# OpenBLC_CONNECTIONS.net
KiCad netlist of a schematic drawn in Altium Designer
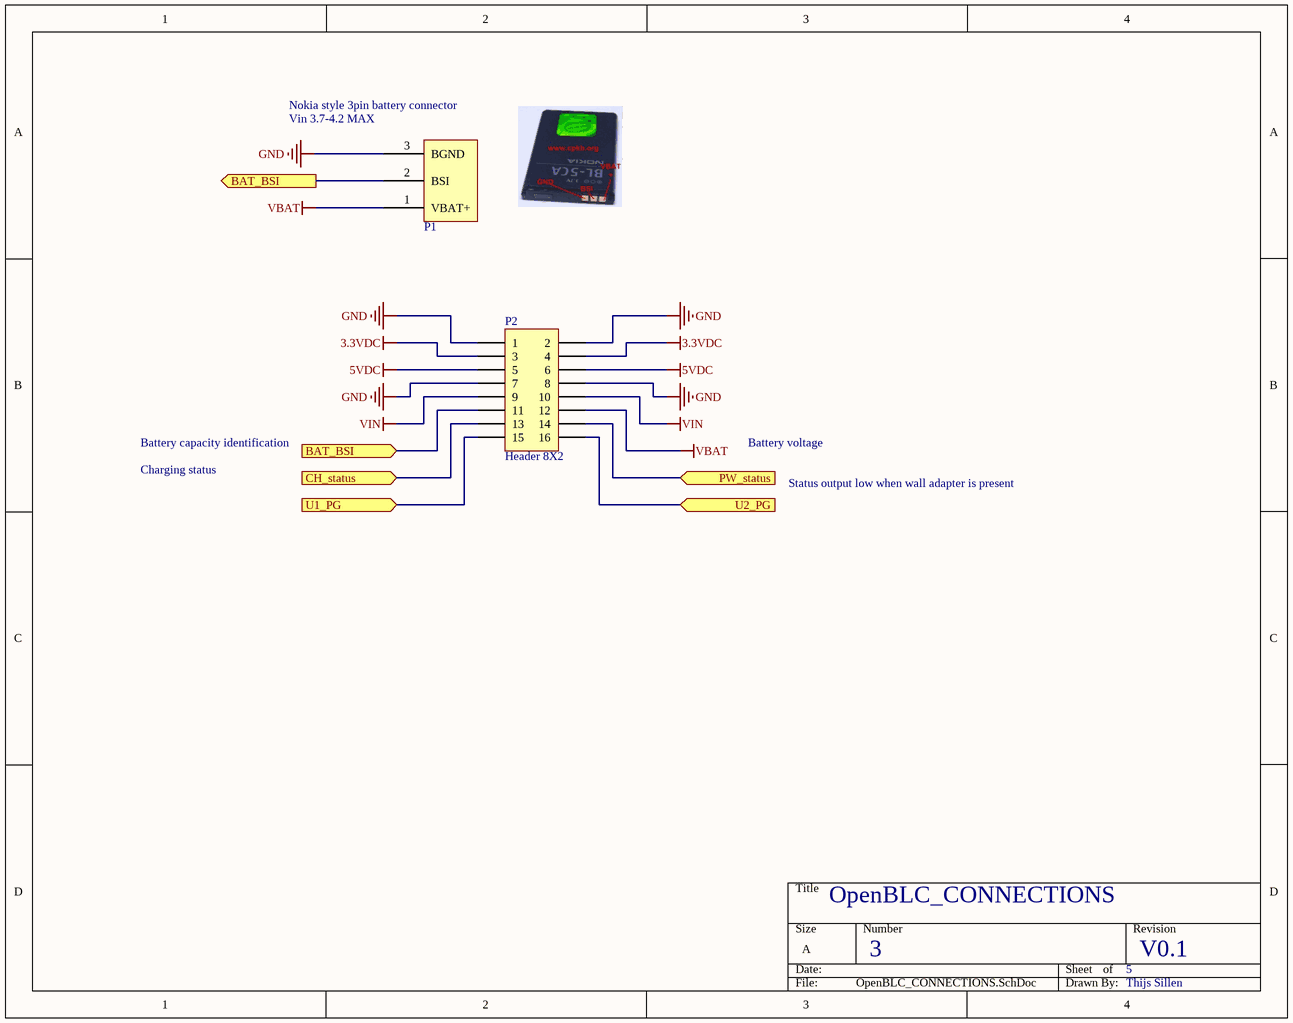
[diagram p0: OpenBLC_CONNECTIONS.SchDoc]

(export (version "E")
  (design (tool "Eeschema 10.0.6"))
  (components
    (comp (ref "P1")
      (value "Nokia 3pin pogo connector")
      (footprint "Nokia_3P_batt_conn")
      (libsource (lib "Schlib1") (part "Nokia_3PIN_BATT_CONTACT"))
    )
    (comp (ref "P2")
      (value "Header 8X2")
      (footprint "HDR2X8")
      (description "Header, 8-Pin, Dual row")
      (fields (field (name "PUBLISHER") "Altium Limited"))
      (libsource (lib "Miscellaneous Connectors") (part "Header 8X2"))
    )
  )
  (nets
    (net (code "1") (name "/BAT_BSI") (class "Default")
      (node (ref "P1") (pin "2") (pinfunction "BSI_2") (pintype "passive"))
      (node (ref "P2") (pin "11") (pinfunction "11_11") (pintype "passive"))
    )
    (net (code "2") (name "/CH_status") (class "Default")
      (node (ref "P2") (pin "13") (pinfunction "13_13") (pintype "passive"))
    )
    (net (code "3") (name "/PW_status") (class "Default")
      (node (ref "P2") (pin "14") (pinfunction "14_14") (pintype "passive"))
    )
    (net (code "4") (name "/U1_PG") (class "Default")
      (node (ref "P2") (pin "15") (pinfunction "15_15") (pintype "passive"))
    )
    (net (code "5") (name "/U2_PG") (class "Default")
      (node (ref "P2") (pin "16") (pinfunction "16_16") (pintype "passive"))
    )
    (net (code "6") (name "3.3VDC") (class "Default")
      (node (ref "P2") (pin "3") (pinfunction "3_3") (pintype "passive"))
      (node (ref "P2") (pin "4") (pinfunction "4_4") (pintype "passive"))
    )
    (net (code "7") (name "5VDC") (class "Default")
      (node (ref "P2") (pin "5") (pinfunction "5_5") (pintype "passive"))
      (node (ref "P2") (pin "6") (pinfunction "6_6") (pintype "passive"))
    )
    (net (code "8") (name "GND") (class "Default")
      (node (ref "P1") (pin "3") (pinfunction "BGND_3") (pintype "passive"))
      (node (ref "P2") (pin "1") (pinfunction "1_1") (pintype "passive"))
      (node (ref "P2") (pin "2") (pinfunction "2_2") (pintype "passive"))
      (node (ref "P2") (pin "7") (pinfunction "7_7") (pintype "passive"))
      (node (ref "P2") (pin "8") (pinfunction "8_8") (pintype "passive"))
    )
    (net (code "9") (name "VBAT") (class "Default")
      (node (ref "P1") (pin "1") (pinfunction "VBAT+_1") (pintype "passive"))
      (node (ref "P2") (pin "12") (pinfunction "12_12") (pintype "passive"))
    )
    (net (code "10") (name "VIN") (class "Default")
      (node (ref "P2") (pin "10") (pinfunction "10_10") (pintype "passive"))
      (node (ref "P2") (pin "9") (pinfunction "9_9") (pintype "passive"))
    )
  )
)
